# ETAG_v6.net
KiCad netlist of a schematic drawn in EAGLE
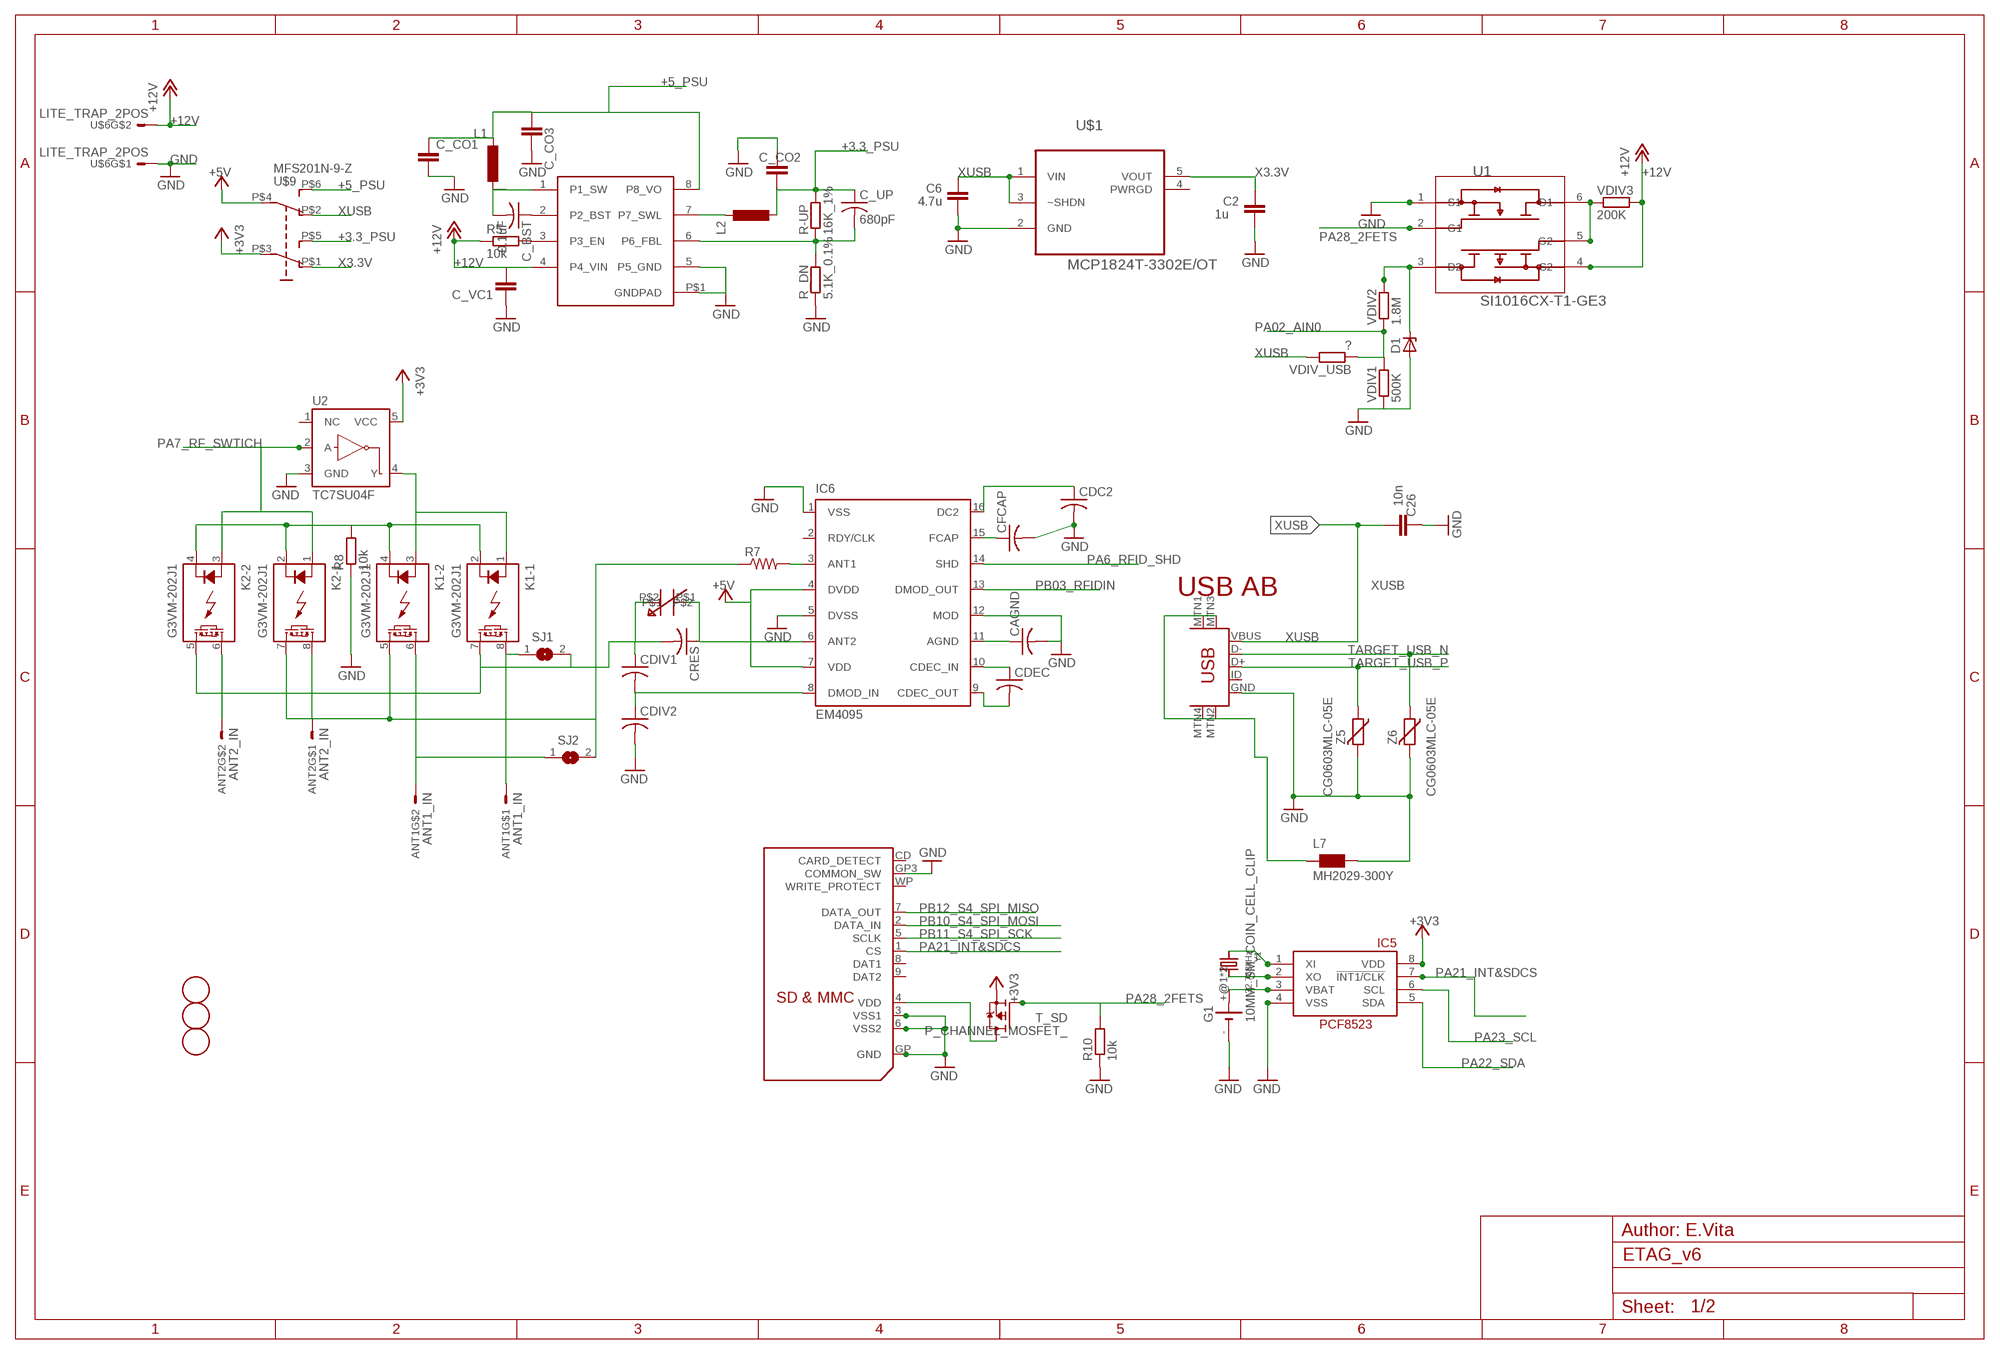
[diagram p0: schematic, sheet 1]
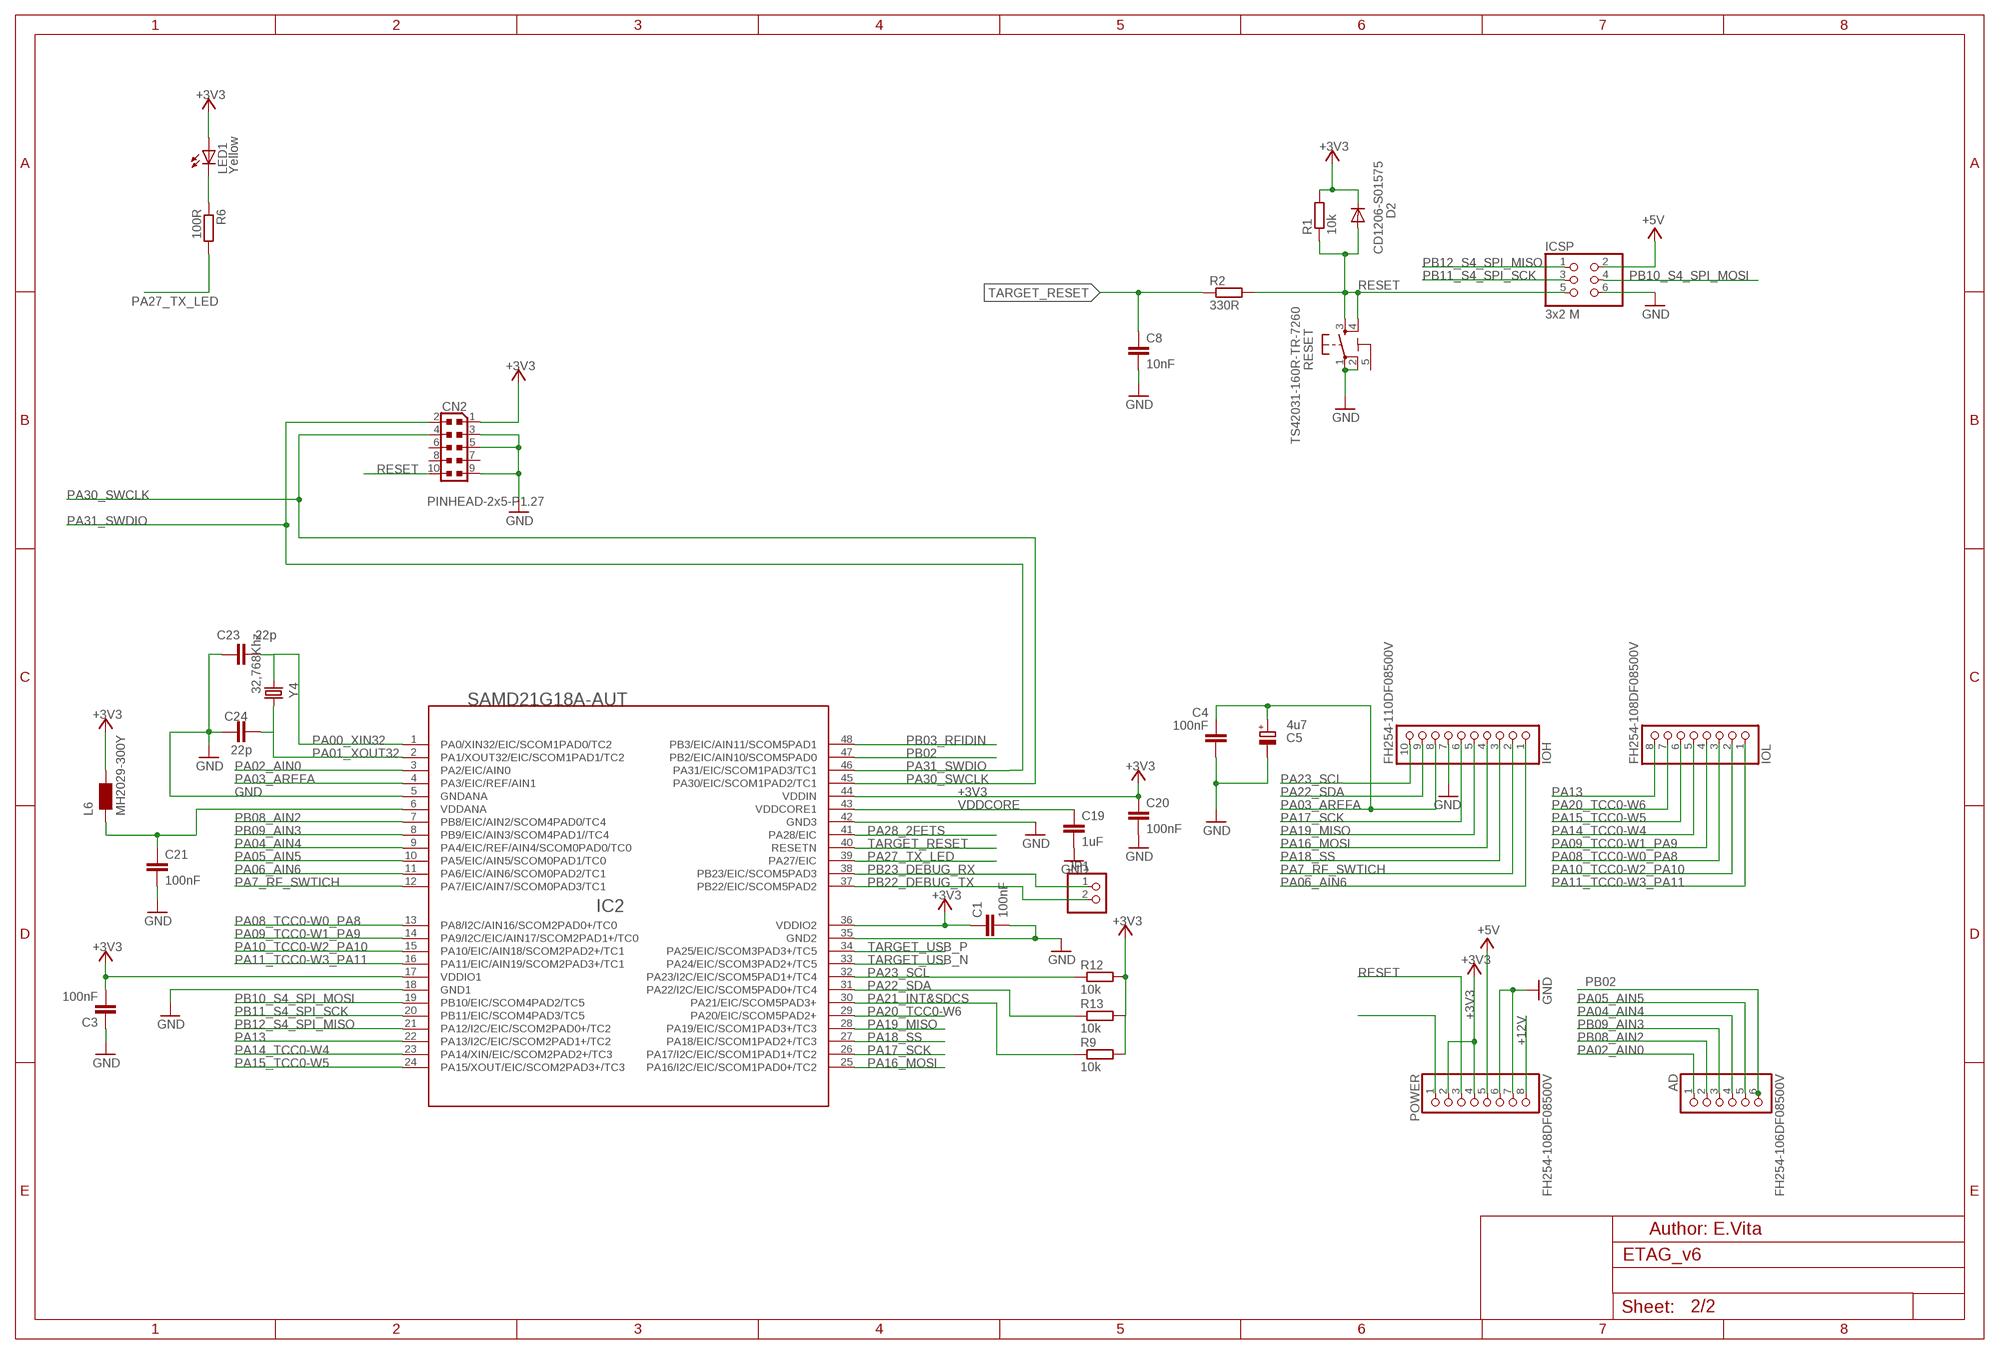
[diagram p1: schematic, sheet 2]

(export (version "E")
  (design (tool "Eeschema 10.0.6"))
  (components
    (comp (ref "AD")
      (value "FH254-106DF08500V")
      (footprint "eagle-import:1X06")
      (fields (field (name "PART_NUMBER") "20TW-535"))
      (libsource (lib "eagle-import") (part "1682_20TW-535_STD"))
    )
    (comp (ref "C1")
      (value "100nF")
      (footprint "eagle-import:C0603-ROUND")
      (fields (field (name "PART_NUMBER") "cl10b104kbnc"))
      (libsource (lib "eagle-import") (part "0015_100NF_0603"))
    )
    (comp (ref "C3")
      (value "100nF")
      (footprint "eagle-import:C0603-ROUND")
      (fields (field (name "PART_NUMBER") "cl10b104kbnc"))
      (libsource (lib "eagle-import") (part "0015_100NF_0603"))
    )
    (comp (ref "C4")
      (value "100nF")
      (footprint "eagle-import:C0603-ROUND")
      (fields (field (name "PART_NUMBER") "cl10b104kbnc"))
      (libsource (lib "eagle-import") (part "0015_100NF_0603"))
    )
    (comp (ref "C5")
      (value "4u7")
      (footprint "eagle-import:SMC_A")
      (fields (field (name "PART_NUMBER") "TAJA475M016RNJ"))
      (libsource (lib "eagle-import") (part "0474_TAJA475M016RNJ"))
    )
    (comp (ref "C8")
      (value "10nF")
      (footprint "eagle-import:C0603-ROUND")
      (fields (field (name "PART_NUMBER") "10nF_0603"))
      (libsource (lib "eagle-import") (part "0142_10NF_0603"))
    )
    (comp (ref "C19")
      (value "1uF")
      (footprint "eagle-import:C0603-ROUND")
      (fields (field (name "PART_NUMBER") "1uF_0603/GRM188R61E105KA12D"))
      (libsource (lib "eagle-import") (part "0006_1UF_0603/GRM188R61E105KA12D"))
    )
    (comp (ref "C20")
      (value "100nF")
      (footprint "eagle-import:C0603-ROUND")
      (fields (field (name "PART_NUMBER") "cl10b104kbnc"))
      (libsource (lib "eagle-import") (part "0015_100NF_0603"))
    )
    (comp (ref "C21")
      (value "100nF")
      (footprint "eagle-import:C0603-ROUND")
      (fields (field (name "PART_NUMBER") "cl10b104kbnc"))
      (libsource (lib "eagle-import") (part "0015_100NF_0603"))
    )
    (comp (ref "C23")
      (value "22p")
      (footprint "eagle-import:C0603-ROUND")
      (fields (field (name "PART_NUMBER") "22pF_0603"))
      (libsource (lib "eagle-import") (part "0014_22PF_0603"))
    )
    (comp (ref "C24")
      (value "22p")
      (footprint "eagle-import:C0603-ROUND")
      (fields (field (name "PART_NUMBER") "22pF_0603"))
      (libsource (lib "eagle-import") (part "0014_22PF_0603"))
    )
    (comp (ref "CN2")
      (value "PINHEAD-2x5-P1.27")
      (footprint "eagle-import:PINHEAD_2X05_127")
      (libsource (lib "eagle-import") (part "0171_PH127-205DF055G00AROUND-PADS"))
    )
    (comp (ref "D2")
      (value "CD1206-S01575")
      (footprint "eagle-import:MINIMELF")
      (libsource (lib "eagle-import") (part "0012_CD1206-S01575"))
    )
    (comp (ref "IC2")
      (value "SAMD21G18A-AUT")
      (footprint "eagle-import:TQFP48-7X7")
      (libsource (lib "eagle-import") (part "1792_SAMD21G18A-AUT"))
    )
    (comp (ref "ICSP")
      (value "3x2 M")
      (footprint "eagle-import:2X03")
      (fields (field (name "PART_NUMBER") "PH254-203DF118A00V"))
      (libsource (lib "eagle-import") (part "0114_PH254-203DF118A00V"))
    )
    (comp (ref "IOH")
      (value "FH254-110DF08500V")
      (footprint "eagle-import:1X10")
      (fields (field (name "PART_NUMBER") "20TW-537"))
      (libsource (lib "eagle-import") (part "1684_20TW-537"))
    )
    (comp (ref "IOL")
      (value "FH254-108DF08500V")
      (footprint "eagle-import:1X08")
      (fields (field (name "PART_NUMBER") "20TW-536"))
      (libsource (lib "eagle-import") (part "1683_20TW-536"))
    )
    (comp (ref "JP1")
      (value "PINHD-1X2")
      (footprint "eagle-import:1X02")
      (libsource (lib "eagle-import") (part "PINHD-1X2"))
    )
    (comp (ref "L6")
      (value "MH2029-300Y")
      (footprint "eagle-import:0805")
      (fields (field (name "PART_NUMBER") "BLM21PG300SN1D_/_MH2029-300Y"))
      (libsource (lib "eagle-import") (part "0001_BLM21PG300SN1D_/_MH2029-300Y"))
    )
    (comp (ref "LED1")
      (value "Yellow")
      (footprint "eagle-import:CHIPLED_0805")
      (fields (field (name "PART_NUMBER") "KPT-2012YC"))
      (libsource (lib "eagle-import") (part "0044_KPT-2012YC"))
    )
    (comp (ref "POWER")
      (value "FH254-108DF08500V")
      (footprint "eagle-import:1X08")
      (fields (field (name "PART_NUMBER") "20TW-536"))
      (libsource (lib "eagle-import") (part "1683_20TW-536"))
    )
    (comp (ref "R1")
      (value "10k")
      (footprint "eagle-import:R0603-ROUND")
      (fields (field (name "PART_NUMBER") "CR0603JW103L"))
      (libsource (lib "eagle-import") (part "0028_CR0603JW103L"))
    )
    (comp (ref "R2")
      (value "330R")
      (footprint "eagle-import:R0603-ROUND")
      (fields (field (name "PART_NUMBER") "330R_0603"))
      (libsource (lib "eagle-import") (part "0049_330R_0603"))
    )
    (comp (ref "R6")
      (value "100R")
      (footprint "eagle-import:R0603-ROUND")
      (fields (field (name "PART_NUMBER") "0R_0603"))
      (libsource (lib "eagle-import") (part "0233_0R_0603"))
    )
    (comp (ref "R9")
      (value "10k")
      (footprint "eagle-import:R0603-ROUND")
      (fields (field (name "PART_NUMBER") "CR0603JW103L"))
      (libsource (lib "eagle-import") (part "0028_CR0603JW103L"))
    )
    (comp (ref "R12")
      (value "10k")
      (footprint "eagle-import:R0603-ROUND")
      (fields (field (name "PART_NUMBER") "CR0603JW103L"))
      (libsource (lib "eagle-import") (part "0028_CR0603JW103L"))
    )
    (comp (ref "R13")
      (value "10k")
      (footprint "eagle-import:R0603-ROUND")
      (fields (field (name "PART_NUMBER") "CR0603JW103L"))
      (libsource (lib "eagle-import") (part "0028_CR0603JW103L"))
    )
    (comp (ref "RESET")
      (value "TS42031-160R-TR-7260")
      (footprint "eagle-import:TS42")
      (fields (field (name "PART_NUMBER") "IT-1157AHNP-160G-G_GTR"))
      (libsource (lib "eagle-import") (part "0946_TS42031-160W-TR-7260"))
    )
    (comp (ref "Y4")
      (value "32,768Khz")
      (footprint "eagle-import:RESONATOR_EPSON_FC_145")
      (fields (field (name "PART_NUMBER") "ABS07-32.768KHZ-T"))
      (libsource (lib "eagle-import") (part "0213_ABS07-32.768KHZ-T"))
    )
    (comp (ref "ANT1")
      (value "ANT1_IN")
      (footprint "eagle-import:LITE_TRAP_MINI")
      (libsource (lib "eagle-import") (part "LITE_TRAP_2POS"))
    )
    (comp (ref "ANT2")
      (value "ANT2_IN")
      (footprint "eagle-import:LITE_TRAP_MINI")
      (libsource (lib "eagle-import") (part "LITE_TRAP_2POS"))
    )
    (comp (ref "C2")
      (value "1u")
      (footprint "eagle-import:C0603-ROUND")
      (fields (field (name "PART_NUMBER") "10nF_0603"))
      (libsource (lib "eagle-import") (part "0142_10NF_0603"))
    )
    (comp (ref "C6")
      (value "4.7u")
      (footprint "eagle-import:C0603-ROUND")
      (fields (field (name "PART_NUMBER") "10nF_0603"))
      (libsource (lib "eagle-import") (part "0142_10NF_0603"))
    )
    (comp (ref "C26")
      (value "10n")
      (footprint "eagle-import:C0603-ROUND")
      (fields (field (name "PART_NUMBER") "10nF_0603"))
      (libsource (lib "eagle-import") (part "0142_10NF_0603"))
    )
    (comp (ref "CAGND")
      (value "C-US")
      (footprint "eagle-import:C0603-ROUND")
      (libsource (lib "eagle-import") (part "C-US"))
    )
    (comp (ref "CDC2")
      (value "C-US")
      (footprint "eagle-import:C0603-ROUND")
      (libsource (lib "eagle-import") (part "C-US"))
    )
    (comp (ref "CDEC")
      (value "C-US")
      (footprint "eagle-import:C0603-ROUND")
      (libsource (lib "eagle-import") (part "C-US"))
    )
    (comp (ref "CDIV1")
      (value "C-USC1206K")
      (footprint "eagle-import:C1206K")
      (libsource (lib "eagle-import") (part "C-USC1206K"))
    )
    (comp (ref "CDIV2")
      (value "C-USC1206K")
      (footprint "eagle-import:C1206K")
      (libsource (lib "eagle-import") (part "C-USC1206K"))
    )
    (comp (ref "CFCAP")
      (value "C-US")
      (footprint "eagle-import:C0603-ROUND")
      (libsource (lib "eagle-import") (part "C-US"))
    )
    (comp (ref "CRES")
      (value "C-USC1206K")
      (footprint "eagle-import:C1206K")
      (libsource (lib "eagle-import") (part "C-USC1206K"))
    )
    (comp (ref "C_BST")
      (value "0.1uF")
      (footprint "eagle-import:C0603-ROUND")
      (libsource (lib "eagle-import") (part "C-US"))
    )
    (comp (ref "C_CO1")
      (value "22uF")
      (footprint "eagle-import:C0805")
      (libsource (lib "eagle-import") (part "C-EUC0805"))
    )
    (comp (ref "C_CO2")
      (value "22uF")
      (footprint "eagle-import:C0805")
      (libsource (lib "eagle-import") (part "C-EUC0805"))
    )
    (comp (ref "C_CO3")
      (value "10uF")
      (footprint "eagle-import:C0805")
      (libsource (lib "eagle-import") (part "C-EUC0805"))
    )
    (comp (ref "C_UP")
      (value "680pF")
      (footprint "eagle-import:C0603-ROUND")
      (libsource (lib "eagle-import") (part "C-US"))
    )
    (comp (ref "C_VC1")
      (value "10uF")
      (footprint "eagle-import:C1210")
      (libsource (lib "eagle-import") (part "C-EUC1210"))
    )
    (comp (ref "D1")
      (value "ZENER-DIODESOD123")
      (footprint "eagle-import:SOD123FL")
      (libsource (lib "eagle-import") (part "ZENER-DIODESOD123"))
    )
    (comp (ref "FD1")
      (value "FIDUCIALMOUNT")
      (footprint "eagle-import:FIDUCIA-MOUNT")
      (libsource (lib "eagle-import") (part "FIDUCIALMOUNT"))
    )
    (comp (ref "FD2")
      (value "FIDUCIALMOUNT")
      (footprint "eagle-import:FIDUCIA-MOUNT")
      (libsource (lib "eagle-import") (part "FIDUCIALMOUNT"))
    )
    (comp (ref "FD3")
      (value "FIDUCIALMOUNT")
      (footprint "eagle-import:FIDUCIA-MOUNT")
      (libsource (lib "eagle-import") (part "FIDUCIALMOUNT"))
    )
    (comp (ref "G1")
      (value "10MM_SM_COIN_CELL_CLIP")
      (footprint "eagle-import:10MM_SM_COIN_CELL_CLIP")
      (libsource (lib "eagle-import") (part "10MM_SM_COIN_CELL_CLIP"))
    )
    (comp (ref "IC5")
      (value "RTC_PCF8523T")
      (footprint "eagle-import:SOIC8_150MIL")
      (libsource (lib "eagle-import") (part "RTC_PCF8523T"))
    )
    (comp (ref "IC6")
      (value "EM4095")
      (footprint "eagle-import:SO16")
      (libsource (lib "eagle-import") (part "EM4095"))
    )
    (comp (ref "K1")
      (value "G3VM-202J1")
      (footprint "eagle-import:SOP08")
      (libsource (lib "eagle-import") (part "AQWSOP21"))
    )
    (comp (ref "K2")
      (value "G3VM-202J1")
      (footprint "eagle-import:SOP08")
      (libsource (lib "eagle-import") (part "AQWSOP21"))
    )
    (comp (ref "L1")
      (value "22uH")
      (footprint "eagle-import:SLF10165")
      (libsource (lib "eagle-import") (part "L-EUSLF_10MM"))
    )
    (comp (ref "L2")
      (value "2.2uH")
      (footprint "eagle-import:L1008(2520METRIC)")
      (libsource (lib "eagle-import") (part "L-EU1008"))
    )
    (comp (ref "L7")
      (value "MH2029-300Y")
      (footprint "eagle-import:0805")
      (fields (field (name "PART_NUMBER") "BLM21PG300SN1D_/_MH2029-300Y"))
      (libsource (lib "eagle-import") (part "0001_BLM21PG300SN1D_/_MH2029-300Y"))
    )
    (comp (ref "R-UP")
      (value "16K_1%")
      (footprint "eagle-import:R0603-ROUND")
      (fields (field (name "PART_NUMBER") "CR0603FW104L"))
      (libsource (lib "eagle-import") (part "2022_CR0603FW104L"))
    )
    (comp (ref "R5")
      (value "10k")
      (footprint "eagle-import:R0603-ROUND")
      (fields (field (name "PART_NUMBER") "CR0603JW103L"))
      (libsource (lib "eagle-import") (part "0028_CR0603JW103L"))
    )
    (comp (ref "R7")
      (value "R-US_R1206")
      (footprint "eagle-import:R1206")
      (libsource (lib "eagle-import") (part "R-US_R1206"))
    )
    (comp (ref "R8")
      (value "10k")
      (footprint "eagle-import:R0603-ROUND")
      (fields (field (name "PART_NUMBER") "CR0603JW103L"))
      (libsource (lib "eagle-import") (part "0028_CR0603JW103L"))
    )
    (comp (ref "R10")
      (value "10k")
      (footprint "eagle-import:R0603-ROUND")
      (fields (field (name "PART_NUMBER") "CR0603JW103L"))
      (libsource (lib "eagle-import") (part "0028_CR0603JW103L"))
    )
    (comp (ref "R_DN")
      (value "5.1K_0.1%")
      (footprint "eagle-import:R0603-ROUND")
      (libsource (lib "eagle-import") (part "2339_"))
    )
    (comp (ref "SJ1")
      (value "SJW")
      (footprint "eagle-import:SJW")
      (libsource (lib "eagle-import") (part "SJW"))
    )
    (comp (ref "SJ2")
      (value "SJW")
      (footprint "eagle-import:SJW")
      (libsource (lib "eagle-import") (part "SJW"))
    )
    (comp (ref "T_SD")
      (value "P_CHANNEL_MOSFET_")
      (footprint "eagle-import:SOT23")
      (libsource (lib "eagle-import") (part "P_CHANNEL_MOSFET_"))
    )
    (comp (ref "U$1")
      (value "MCP1824T-3302E/OT")
      (footprint "eagle-import:SOT95P270X145-5N")
      (libsource (lib "eagle-import") (part "MCP1824T-3302E/OT"))
    )
    (comp (ref "U$3")
      (value "BD93291EFJSOP8_W_GND")
      (footprint "eagle-import:SOP08_GNDPAD")
      (libsource (lib "eagle-import") (part "BD93291EFJSOP8_W_GND"))
    )
    (comp (ref "U$4")
      (value "SDMMC06132")
      (footprint "eagle-import:06132")
      (libsource (lib "eagle-import") (part "SDMMC06132"))
    )
    (comp (ref "U$5")
      (value "USB-MINIB-5PIN")
      (footprint "eagle-import:USB-MINIB")
      (libsource (lib "eagle-import") (part "USB-MINIB-5PIN"))
    )
    (comp (ref "U$6")
      (value "LITE_TRAP_2POS")
      (footprint "eagle-import:LITE_TRAP_MINI")
      (libsource (lib "eagle-import") (part "LITE_TRAP_2POS"))
    )
    (comp (ref "U$9")
      (value "MFS201N-9-Z")
      (footprint "eagle-import:MFS201N-9-Z")
      (libsource (lib "eagle-import") (part "MFS201N-9-Z"))
    )
    (comp (ref "U1")
      (value "SI1016CX-T1-GE3")
      (footprint "eagle-import:SOT50P162X60-6N")
      (libsource (lib "eagle-import") (part "SI1016CX-T1-GE3"))
    )
    (comp (ref "U2")
      (value "TC7SU04F")
      (footprint "eagle-import:SOT23-5")
      (libsource (lib "eagle-import") (part "INVERTER_SOT23-5"))
    )
    (comp (ref "VAR_C")
      (value "TZB4Z100AB10R00")
      (footprint "eagle-import:TZB4Z100AB10R00")
      (libsource (lib "eagle-import") (part "TZB4Z100AB10R00"))
    )
    (comp (ref "VDIV1")
      (value "500K")
      (footprint "eagle-import:R0603-ROUND")
      (libsource (lib "eagle-import") (part "2339_"))
    )
    (comp (ref "VDIV2")
      (value "1.8M")
      (footprint "eagle-import:R0603-ROUND")
      (fields (field (name "PART_NUMBER") "CR0603FW104L"))
      (libsource (lib "eagle-import") (part "2022_CR0603FW104L"))
    )
    (comp (ref "VDIV3")
      (value "200K")
      (footprint "eagle-import:R0603-ROUND")
      (fields (field (name "PART_NUMBER") "CR0603FW104L"))
      (libsource (lib "eagle-import") (part "2022_CR0603FW104L"))
    )
    (comp (ref "VDIV_USB")
      (value "?")
      (footprint "eagle-import:R0603-ROUND")
      (libsource (lib "eagle-import") (part "2339_"))
    )
    (comp (ref "Y1")
      (value "32.768kHz")
      (footprint "eagle-import:CRYSTAL_8X3.8")
      (libsource (lib "eagle-import") (part "CRYSTAL8.0X3.8"))
    )
    (comp (ref "Z5")
      (value "CG0603MLC-05E")
      (footprint "eagle-import:CT_CN0603")
      (fields (field (name "PART_NUMBER") "BRNCG0603MLC-05E"))
      (libsource (lib "eagle-import") (part "0010_BRNCG0603MLC-05E"))
    )
    (comp (ref "Z6")
      (value "CG0603MLC-05E")
      (footprint "eagle-import:CT_CN0603")
      (fields (field (name "PART_NUMBER") "BRNCG0603MLC-05E"))
      (libsource (lib "eagle-import") (part "0010_BRNCG0603MLC-05E"))
    )
  )
  (nets
    (net (code "1") (name "+3.3_PSU") (class "Default")
      (node (ref "C_CO2") (pin "2") (pinfunction "2_2") (pintype "passive"))
      (node (ref "C_UP") (pin "1") (pinfunction "1_1") (pintype "passive"))
      (node (ref "L2") (pin "2") (pinfunction "2_2") (pintype "passive"))
      (node (ref "R-UP") (pin "2") (pinfunction "2_2") (pintype "passive"))
      (node (ref "U$9") (pin "P$5") (pinfunction "S_P$5") (pintype "passive"))
    )
    (net (code "2") (name "+3V3") (class "Default")
      (node (ref "C1") (pin "1") (pinfunction "1_1") (pintype "passive"))
      (node (ref "C20") (pin "1") (pinfunction "1_1") (pintype "passive"))
      (node (ref "C3") (pin "2") (pinfunction "2_2") (pintype "passive"))
      (node (ref "CN2") (pin "1") (pinfunction "1_1") (pintype "passive"))
      (node (ref "D2") (pin "C") (pinfunction "C_C") (pintype "passive"))
      (node (ref "IC2") (pin "17") (pinfunction "VDDIO1_17") (pintype "power_in"))
      (node (ref "IC2") (pin "36") (pinfunction "VDDIO2_36") (pintype "power_in"))
      (node (ref "IC2") (pin "44") (pinfunction "VDDIN_44") (pintype "power_in"))
      (node (ref "IC5") (pin "8") (pinfunction "VDD_8") (pintype "power_in"))
      (node (ref "L6") (pin "2") (pinfunction "2_2") (pintype "passive"))
      (node (ref "LED1") (pin "A") (pinfunction "A_A") (pintype "passive"))
      (node (ref "POWER") (pin "2") (pinfunction "2_2") (pintype "passive"))
      (node (ref "POWER") (pin "4") (pinfunction "4_4") (pintype "passive"))
      (node (ref "R1") (pin "2") (pinfunction "2_2") (pintype "passive"))
      (node (ref "R12") (pin "2") (pinfunction "2_2") (pintype "passive"))
      (node (ref "R13") (pin "2") (pinfunction "2_2") (pintype "passive"))
      (node (ref "R9") (pin "2") (pinfunction "2_2") (pintype "passive"))
      (node (ref "T_SD") (pin "2") (pinfunction "S_2") (pintype "passive"))
      (node (ref "U$9") (pin "P$3") (pinfunction "P_P$3") (pintype "passive"))
      (node (ref "U2") (pin "5") (pinfunction "VCC_5") (pintype "bidirectional"))
    )
    (net (code "3") (name "+5V") (class "Default")
      (node (ref "IC6") (pin "4") (pinfunction "DVDD_4") (pintype "power_in"))
      (node (ref "IC6") (pin "7") (pinfunction "VDD_7") (pintype "power_in"))
      (node (ref "ICSP") (pin "2") (pinfunction "2_2") (pintype "passive"))
      (node (ref "POWER") (pin "5") (pinfunction "5_5") (pintype "passive"))
      (node (ref "U$9") (pin "P$4") (pinfunction "P1_P$4") (pintype "passive"))
    )
    (net (code "4") (name "+5_PSU") (class "Default")
      (node (ref "C_CO1") (pin "1") (pinfunction "1_1") (pintype "passive"))
      (node (ref "C_CO3") (pin "1") (pinfunction "1_1") (pintype "passive"))
      (node (ref "L1") (pin "P$1") (pinfunction "1_P$1") (pintype "passive"))
      (node (ref "U$3") (pin "8") (pinfunction "P8_VO_8") (pintype "bidirectional"))
      (node (ref "U$9") (pin "P$6") (pinfunction "S1_P$6") (pintype "passive"))
    )
    (net (code "5") (name "+12V") (class "Default")
      (node (ref "C_VC1") (pin "2") (pinfunction "2_2") (pintype "passive"))
      (node (ref "POWER") (pin "8") (pinfunction "8_8") (pintype "passive"))
      (node (ref "R5") (pin "1") (pinfunction "1_1") (pintype "passive"))
      (node (ref "U$3") (pin "4") (pinfunction "P4_VIN_4") (pintype "bidirectional"))
      (node (ref "U$6") (pin "P$3") (pinfunction "S_P$3") (pintype "passive"))
      (node (ref "U$6") (pin "P$4") (pinfunction "S_P$4") (pintype "passive"))
      (node (ref "U1") (pin "4") (pinfunction "S2_4") (pintype "passive"))
      (node (ref "VDIV3") (pin "2") (pinfunction "2_2") (pintype "passive"))
    )
    (net (code "6") (name "5-GND") (class "Default")
      (node (ref "RESET") (pin "5") (pinfunction "5-GND_5") (pintype "power_in"))
    )
    (net (code "7") (name "GND") (class "Default")
      (node (ref "C1") (pin "2") (pinfunction "2_2") (pintype "passive"))
      (node (ref "C19") (pin "2") (pinfunction "2_2") (pintype "passive"))
      (node (ref "C2") (pin "1") (pinfunction "1_1") (pintype "passive"))
      (node (ref "C20") (pin "2") (pinfunction "2_2") (pintype "passive"))
      (node (ref "C21") (pin "2") (pinfunction "2_2") (pintype "passive"))
      (node (ref "C23") (pin "1") (pinfunction "1_1") (pintype "passive"))
      (node (ref "C24") (pin "1") (pinfunction "1_1") (pintype "passive"))
      (node (ref "C26") (pin "2") (pinfunction "2_2") (pintype "passive"))
      (node (ref "C3") (pin "1") (pinfunction "1_1") (pintype "passive"))
      (node (ref "C4") (pin "2") (pinfunction "2_2") (pintype "passive"))
      (node (ref "C5") (pin "-") (pinfunction "-_-") (pintype "passive"))
      (node (ref "C6") (pin "1") (pinfunction "1_1") (pintype "passive"))
      (node (ref "C8") (pin "2") (pinfunction "2_2") (pintype "passive"))
      (node (ref "CAGND") (pin "2") (pinfunction "2_2") (pintype "passive"))
      (node (ref "CDC2") (pin "2") (pinfunction "2_2") (pintype "passive"))
      (node (ref "CDIV2") (pin "2") (pinfunction "2_2") (pintype "passive"))
      (node (ref "CFCAP") (pin "2") (pinfunction "2_2") (pintype "passive"))
      (node (ref "CN2") (pin "3") (pinfunction "3_3") (pintype "passive"))
      (node (ref "CN2") (pin "5") (pinfunction "5_5") (pintype "passive"))
      (node (ref "CN2") (pin "9") (pinfunction "9_9") (pintype "passive"))
      (node (ref "C_CO1") (pin "2") (pinfunction "2_2") (pintype "passive"))
      (node (ref "C_CO2") (pin "1") (pinfunction "1_1") (pintype "passive"))
      (node (ref "C_CO3") (pin "2") (pinfunction "2_2") (pintype "passive"))
      (node (ref "C_VC1") (pin "1") (pinfunction "1_1") (pintype "passive"))
      (node (ref "D1") (pin "A") (pinfunction "A_A") (pintype "passive"))
      (node (ref "G1") (pin "-") (pinfunction "-_-") (pintype "passive"))
      (node (ref "IC2") (pin "18") (pinfunction "GND1_18") (pintype "power_in"))
      (node (ref "IC2") (pin "35") (pinfunction "GND2_35") (pintype "power_in"))
      (node (ref "IC2") (pin "42") (pinfunction "GND3_42") (pintype "power_in"))
      (node (ref "IC2") (pin "5") (pinfunction "GNDANA_5") (pintype "power_in"))
      (node (ref "IC5") (pin "4") (pinfunction "VSS_4") (pintype "power_in"))
      (node (ref "IC6") (pin "1") (pinfunction "VSS_1") (pintype "power_in"))
      (node (ref "IC6") (pin "12") (pinfunction "MOD_12") (pintype "input"))
      (node (ref "IC6") (pin "5") (pinfunction "DVSS_5") (pintype "power_in"))
      (node (ref "ICSP") (pin "6") (pinfunction "6_6") (pintype "passive"))
      (node (ref "IOH") (pin "7") (pinfunction "7_7") (pintype "passive"))
      (node (ref "L7") (pin "2") (pinfunction "2_2") (pintype "passive"))
      (node (ref "POWER") (pin "6") (pinfunction "6_6") (pintype "passive"))
      (node (ref "POWER") (pin "7") (pinfunction "7_7") (pintype "passive"))
      (node (ref "R10") (pin "1") (pinfunction "1_1") (pintype "passive"))
      (node (ref "R8") (pin "1") (pinfunction "1_1") (pintype "passive"))
      (node (ref "RESET") (pin "1") (pinfunction "1_1") (pintype "passive"))
      (node (ref "RESET") (pin "2") (pinfunction "2_2") (pintype "passive"))
      (node (ref "R_DN") (pin "1") (pinfunction "1_1") (pintype "passive"))
      (node (ref "U$1") (pin "2") (pinfunction "GND_2") (pintype "passive"))
      (node (ref "U$3") (pin "5") (pinfunction "P5_GND_5") (pintype "bidirectional"))
      (node (ref "U$3") (pin "P$1") (pinfunction "GNDPAD_P$1") (pintype "bidirectional"))
      (node (ref "U$4") (pin "3") (pinfunction "VSS1_3") (pintype "power_in"))
      (node (ref "U$4") (pin "6") (pinfunction "VSS2_6") (pintype "power_in"))
      (node (ref "U$4") (pin "GP") (pinfunction "GND_GP") (pintype "power_in"))
      (node (ref "U$4") (pin "GP3") (pinfunction "COMMON_SW_GP3") (pintype "passive"))
      (node (ref "U$5") (pin "GND") (pinfunction "GND_GND") (pintype "bidirectional"))
      (node (ref "U$6") (pin "P$1") (pinfunction "S_P$1") (pintype "passive"))
      (node (ref "U$6") (pin "P$2") (pinfunction "S_P$2") (pintype "passive"))
      (node (ref "U1") (pin "1") (pinfunction "S1_1") (pintype "passive"))
      (node (ref "U2") (pin "3") (pinfunction "GND_3") (pintype "bidirectional"))
      (node (ref "VDIV1") (pin "1") (pinfunction "1_1") (pintype "passive"))
      (node (ref "Z5") (pin "2") (pinfunction "2_2") (pintype "passive"))
      (node (ref "Z6") (pin "2") (pinfunction "2_2") (pintype "passive"))
    )
    (net (code "8") (name "Net-(IC2-VDDANA)") (class "Default")
      (node (ref "C21") (pin "1") (pinfunction "1_1") (pintype "passive"))
      (node (ref "IC2") (pin "6") (pinfunction "VDDANA_6") (pintype "power_in"))
      (node (ref "L6") (pin "1") (pinfunction "1_1") (pintype "passive"))
    )
    (net (code "9") (name "Net-(IC5-VBAT)") (class "Default")
      (node (ref "G1") (pin "+@1") (pinfunction "+_+@1") (pintype "passive"))
      (node (ref "G1") (pin "+@2") (pinfunction "+_+@2") (pintype "passive"))
      (node (ref "IC5") (pin "3") (pinfunction "VBAT_3") (pintype "power_in"))
    )
    (net (code "10") (name "Net-(IC5-XI)") (class "Default")
      (node (ref "IC5") (pin "1") (pinfunction "XI_1") (pintype "input"))
      (node (ref "Y1") (pin "P$1") (pinfunction "1_P$1") (pintype "passive"))
    )
    (net (code "11") (name "Net-(IC5-XO)") (class "Default")
      (node (ref "IC5") (pin "2") (pinfunction "XO_2") (pintype "output"))
      (node (ref "Y1") (pin "P$4") (pinfunction "2_P$4") (pintype "passive"))
    )
    (net (code "12") (name "Net-(IC6-AGND)") (class "Default")
      (node (ref "CAGND") (pin "1") (pinfunction "1_1") (pintype "passive"))
      (node (ref "IC6") (pin "11") (pinfunction "AGND_11") (pintype "power_in"))
    )
    (net (code "13") (name "Net-(IC6-ANT1)") (class "Default")
      (node (ref "IC6") (pin "3") (pinfunction "ANT1_3") (pintype "passive"))
      (node (ref "R7") (pin "2") (pinfunction "2_2") (pintype "passive"))
    )
    (net (code "14") (name "Net-(IC6-ANT2)") (class "Default")
      (node (ref "CRES") (pin "1") (pinfunction "1_1") (pintype "passive"))
      (node (ref "IC6") (pin "6") (pinfunction "ANT2_6") (pintype "passive"))
      (node (ref "VAR_C") (pin "P$1") (pinfunction "P$1_P$1") (pintype "bidirectional"))
    )
    (net (code "15") (name "Net-(IC6-CDEC_IN)") (class "Default")
      (node (ref "CDEC") (pin "1") (pinfunction "1_1") (pintype "passive"))
      (node (ref "IC6") (pin "10") (pinfunction "CDEC_IN_10") (pintype "input"))
    )
    (net (code "16") (name "Net-(IC6-CDEC_OUT)") (class "Default")
      (node (ref "CDEC") (pin "2") (pinfunction "2_2") (pintype "passive"))
      (node (ref "IC6") (pin "9") (pinfunction "CDEC_OUT_9") (pintype "output"))
    )
    (net (code "17") (name "Net-(IC6-DC2)") (class "Default")
      (node (ref "CDC2") (pin "1") (pinfunction "1_1") (pintype "passive"))
      (node (ref "IC6") (pin "16") (pinfunction "DC2_16") (pintype "passive"))
    )
    (net (code "18") (name "Net-(IC6-DMOD_IN)") (class "Default")
      (node (ref "CDIV1") (pin "2") (pinfunction "2_2") (pintype "passive"))
      (node (ref "CDIV2") (pin "1") (pinfunction "1_1") (pintype "passive"))
      (node (ref "IC6") (pin "8") (pinfunction "DMOD_IN_8") (pintype "input"))
    )
    (net (code "19") (name "Net-(IC6-FCAP)") (class "Default")
      (node (ref "CFCAP") (pin "1") (pinfunction "1_1") (pintype "passive"))
      (node (ref "IC6") (pin "15") (pinfunction "FCAP_15") (pintype "passive"))
    )
    (net (code "20") (name "Net-(K1A-A)") (class "Default")
      (node (ref "K1") (pin "1") (pinfunction "A_1") (pintype "passive"))
      (node (ref "K1") (pin "3") (pinfunction "A_3") (pintype "passive"))
      (node (ref "U2") (pin "4") (pinfunction "Y_4") (pintype "bidirectional"))
    )
    (net (code "21") (name "Net-(K1A-D1)") (class "Default")
      (node (ref "ANT1") (pin "P$1") (pinfunction "S_P$1") (pintype "passive"))
      (node (ref "ANT1") (pin "P$2") (pinfunction "S_P$2") (pintype "passive"))
      (node (ref "K1") (pin "8") (pinfunction "D1_8") (pintype "passive"))
      (node (ref "SJ1") (pin "1") (pinfunction "1_1") (pintype "passive"))
    )
    (net (code "22") (name "Net-(K1A-D2)") (class "Default")
      (node (ref "CDIV1") (pin "1") (pinfunction "1_1") (pintype "passive"))
      (node (ref "CRES") (pin "2") (pinfunction "2_2") (pintype "passive"))
      (node (ref "K1") (pin "7") (pinfunction "D2_7") (pintype "passive"))
      (node (ref "K2") (pin "5") (pinfunction "D2_5") (pintype "passive"))
      (node (ref "SJ1") (pin "2") (pinfunction "2_2") (pintype "passive"))
      (node (ref "VAR_C") (pin "P$2") (pinfunction "P$2_P$2") (pintype "bidirectional"))
    )
    (net (code "23") (name "Net-(K1A-K)") (class "Default")
      (node (ref "K1") (pin "2") (pinfunction "K_2") (pintype "passive"))
      (node (ref "K1") (pin "4") (pinfunction "K_4") (pintype "passive"))
      (node (ref "K2") (pin "2") (pinfunction "K_2") (pintype "passive"))
      (node (ref "K2") (pin "4") (pinfunction "K_4") (pintype "passive"))
      (node (ref "R8") (pin "2") (pinfunction "2_2") (pintype "passive"))
    )
    (net (code "24") (name "Net-(K1B-D1)") (class "Default")
      (node (ref "ANT1") (pin "P$3") (pinfunction "S_P$3") (pintype "passive"))
      (node (ref "ANT1") (pin "P$4") (pinfunction "S_P$4") (pintype "passive"))
      (node (ref "K1") (pin "6") (pinfunction "D1_6") (pintype "passive"))
      (node (ref "SJ2") (pin "1") (pinfunction "1_1") (pintype "passive"))
    )
    (net (code "25") (name "Net-(K1B-D2)") (class "Default")
      (node (ref "K1") (pin "5") (pinfunction "D2_5") (pintype "passive"))
      (node (ref "K2") (pin "7") (pinfunction "D2_7") (pintype "passive"))
      (node (ref "R7") (pin "1") (pinfunction "1_1") (pintype "passive"))
      (node (ref "SJ2") (pin "2") (pinfunction "2_2") (pintype "passive"))
    )
    (net (code "26") (name "Net-(K2A-D1)") (class "Default")
      (node (ref "ANT2") (pin "P$1") (pinfunction "S_P$1") (pintype "passive"))
      (node (ref "ANT2") (pin "P$2") (pinfunction "S_P$2") (pintype "passive"))
      (node (ref "K2") (pin "8") (pinfunction "D1_8") (pintype "passive"))
    )
    (net (code "27") (name "Net-(K2B-D1)") (class "Default")
      (node (ref "ANT2") (pin "P$3") (pinfunction "S_P$3") (pintype "passive"))
      (node (ref "ANT2") (pin "P$4") (pinfunction "S_P$4") (pintype "passive"))
      (node (ref "K2") (pin "6") (pinfunction "D1_6") (pintype "passive"))
    )
    (net (code "28") (name "Net-(L1-2)") (class "Default")
      (node (ref "C_BST") (pin "2") (pinfunction "2_2") (pintype "passive"))
      (node (ref "L1") (pin "P$2") (pinfunction "2_P$2") (pintype "passive"))
      (node (ref "U$3") (pin "1") (pinfunction "P1_SW_1") (pintype "bidirectional"))
    )
    (net (code "29") (name "Net-(LED1-PadC)") (class "Default")
      (node (ref "LED1") (pin "C") (pinfunction "C_C") (pintype "passive"))
      (node (ref "R6") (pin "1") (pinfunction "1_1") (pintype "passive"))
    )
    (net (code "30") (name "Net-(T_SD-D)") (class "Default")
      (node (ref "T_SD") (pin "3") (pinfunction "D_3") (pintype "passive"))
      (node (ref "U$4") (pin "4") (pinfunction "VDD_4") (pintype "power_in"))
    )
    (net (code "31") (name "Net-(U$3-P2_BST)") (class "Default")
      (node (ref "C_BST") (pin "1") (pinfunction "1_1") (pintype "passive"))
      (node (ref "U$3") (pin "2") (pinfunction "P2_BST_2") (pintype "bidirectional"))
    )
    (net (code "32") (name "Net-(U$3-P3_EN)") (class "Default")
      (node (ref "R5") (pin "2") (pinfunction "2_2") (pintype "passive"))
      (node (ref "U$3") (pin "3") (pinfunction "P3_EN_3") (pintype "bidirectional"))
    )
    (net (code "33") (name "Net-(U$3-P6_FBL)") (class "Default")
      (node (ref "C_UP") (pin "2") (pinfunction "2_2") (pintype "passive"))
      (node (ref "R-UP") (pin "1") (pinfunction "1_1") (pintype "passive"))
      (node (ref "R_DN") (pin "2") (pinfunction "2_2") (pintype "passive"))
      (node (ref "U$3") (pin "6") (pinfunction "P6_FBL_6") (pintype "bidirectional"))
    )
    (net (code "34") (name "Net-(U$3-P7_SWL)") (class "Default")
      (node (ref "L2") (pin "1") (pinfunction "1_1") (pintype "passive"))
      (node (ref "U$3") (pin "7") (pinfunction "P7_SWL_7") (pintype "bidirectional"))
    )
    (net (code "35") (name "Net-(U$5-MTN1)") (class "Default")
      (node (ref "L7") (pin "1") (pinfunction "1_1") (pintype "passive"))
      (node (ref "U$5") (pin "MTN1") (pinfunction "MTN2_MTN1") (pintype "bidirectional"))
      (node (ref "U$5") (pin "MTN2") (pinfunction "MTN3_MTN2") (pintype "bidirectional"))
      (node (ref "U$5") (pin "MTN3") (pinfunction "MTN1_MTN3") (pintype "bidirectional"))
      (node (ref "U$5") (pin "MTN4") (pinfunction "MTN4_MTN4") (pintype "bidirectional"))
    )
    (net (code "36") (name "Net-(U1-D1)") (class "Default")
      (node (ref "U1") (pin "5") (pinfunction "G2_5") (pintype "passive"))
      (node (ref "U1") (pin "6") (pinfunction "D1_6") (pintype "passive"))
      (node (ref "VDIV3") (pin "1") (pinfunction "1_1") (pintype "passive"))
    )
    (net (code "37") (name "Net-(U1-D2)") (class "Default")
      (node (ref "D1") (pin "C") (pinfunction "C_C") (pintype "passive"))
      (node (ref "U1") (pin "3") (pinfunction "D2_3") (pintype "passive"))
      (node (ref "VDIV2") (pin "2") (pinfunction "2_2") (pintype "passive"))
    )
    (net (code "38") (name "PA00_XIN32") (class "Default")
      (node (ref "C23") (pin "2") (pinfunction "2_2") (pintype "passive"))
      (node (ref "IC2") (pin "1") (pinfunction "PA0/XIN32/EIC/SCOM1PAD0/TC2_1") (pintype "bidirectional"))
      (node (ref "Y4") (pin "P$1") (pinfunction "1_P$1") (pintype "bidirectional"))
    )
    (net (code "39") (name "PA01_XOUT32") (class "Default")
      (node (ref "C24") (pin "2") (pinfunction "2_2") (pintype "passive"))
      (node (ref "IC2") (pin "2") (pinfunction "PA1/XOUT32/EIC/SCOM1PAD1/TC2_2") (pintype "bidirectional"))
      (node (ref "Y4") (pin "P$2") (pinfunction "2_P$2") (pintype "bidirectional"))
    )
    (net (code "40") (name "PA02_AIN0") (class "Default")
      (node (ref "AD") (pin "1") (pinfunction "1_1") (pintype "passive"))
      (node (ref "IC2") (pin "3") (pinfunction "PA2/EIC/AIN0_3") (pintype "bidirectional"))
      (node (ref "VDIV1") (pin "2") (pinfunction "2_2") (pintype "passive"))
      (node (ref "VDIV2") (pin "1") (pinfunction "1_1") (pintype "passive"))
      (node (ref "VDIV_USB") (pin "1") (pinfunction "1_1") (pintype "passive"))
    )
    (net (code "41") (name "PA03_AREFA") (class "Default")
      (node (ref "C4") (pin "1") (pinfunction "1_1") (pintype "passive"))
      (node (ref "C5") (pin "+") (pinfunction "+_+") (pintype "passive"))
      (node (ref "IC2") (pin "4") (pinfunction "PA3/EIC/REF/AIN1_4") (pintype "bidirectional"))
      (node (ref "IOH") (pin "8") (pinfunction "8_8") (pintype "passive"))
    )
    (net (code "42") (name "PA04_AIN4") (class "Default")
      (node (ref "AD") (pin "4") (pinfunction "4_4") (pintype "passive"))
      (node (ref "IC2") (pin "9") (pinfunction "PA4/EIC/REF/AIN4/SCOM0PAD0/TC0_9") (pintype "bidirectional"))
    )
    (net (code "43") (name "PA05_AIN5") (class "Default")
      (node (ref "AD") (pin "5") (pinfunction "5_5") (pintype "passive"))
      (node (ref "IC2") (pin "10") (pinfunction "PA5/EIC/AIN5/SCOM0PAD1/TC0_10") (pintype "bidirectional"))
    )
    (net (code "44") (name "PA06_AIN6") (class "Default")
      (node (ref "IC2") (pin "11") (pinfunction "PA6/EIC/AIN6/SCOM0PAD2/TC1_11") (pintype "bidirectional"))
      (node (ref "IOH") (pin "1") (pinfunction "1_1") (pintype "passive"))
    )
    (net (code "45") (name "PA6_RFID_SHD") (class "Default")
      (node (ref "IC6") (pin "14") (pinfunction "SHD_14") (pintype "input"))
    )
    (net (code "46") (name "PA7_RF_SWTICH") (class "Default")
      (node (ref "IC2") (pin "12") (pinfunction "PA7/EIC/AIN7/SCOM0PAD3/TC1_12") (pintype "bidirectional"))
      (node (ref "IOH") (pin "2") (pinfunction "2_2") (pintype "passive"))
      (node (ref "K2") (pin "1") (pinfunction "A_1") (pintype "passive"))
      (node (ref "K2") (pin "3") (pinfunction "A_3") (pintype "passive"))
      (node (ref "U2") (pin "2") (pinfunction "A_2") (pintype "bidirectional"))
    )
    (net (code "47") (name "PA08_TCC0-W0_PA8") (class "Default")
      (node (ref "IC2") (pin "13") (pinfunction "PA8/I2C/AIN16/SCOM2PAD0+/TC0_13") (pintype "bidirectional"))
      (node (ref "IOL") (pin "3") (pinfunction "3_3") (pintype "passive"))
    )
    (net (code "48") (name "PA09_TCC0-W1_PA9") (class "Default")
      (node (ref "IC2") (pin "14") (pinfunction "PA9/I2C/EIC/AIN17/SCOM2PAD1+/TC0_14") (pintype "bidirectional"))
      (node (ref "IOL") (pin "4") (pinfunction "4_4") (pintype "passive"))
    )
    (net (code "49") (name "PA10_TCC0-W2_PA10") (class "Default")
      (node (ref "IC2") (pin "15") (pinfunction "PA10/EIC/AIN18/SCOM2PAD2+/TC1_15") (pintype "bidirectional"))
      (node (ref "IOL") (pin "2") (pinfunction "2_2") (pintype "passive"))
    )
    (net (code "50") (name "PA11_TCC0-W3_PA11") (class "Default")
      (node (ref "IC2") (pin "16") (pinfunction "PA11/EIC/AIN19/SCOM2PAD3+/TC1_16") (pintype "bidirectional"))
      (node (ref "IOL") (pin "1") (pinfunction "1_1") (pintype "passive"))
    )
    (net (code "51") (name "PA13") (class "Default")
      (node (ref "IC2") (pin "22") (pinfunction "PA13/I2C/EIC/SCOM2PAD1+/TC2_22") (pintype "bidirectional"))
      (node (ref "IOL") (pin "8") (pinfunction "8_8") (pintype "passive"))
    )
    (net (code "52") (name "PA14_TCC0-W4") (class "Default")
      (node (ref "IC2") (pin "23") (pinfunction "PA14/XIN/EIC/SCOM2PAD2+/TC3_23") (pintype "bidirectional"))
      (node (ref "IOL") (pin "5") (pinfunction "5_5") (pintype "passive"))
    )
    (net (code "53") (name "PA15_TCC0-W5") (class "Default")
      (node (ref "IC2") (pin "24") (pinfunction "PA15/XOUT/EIC/SCOM2PAD3+/TC3_24") (pintype "bidirectional"))
      (node (ref "IOL") (pin "6") (pinfunction "6_6") (pintype "passive"))
    )
    (net (code "54") (name "PA16_MOSI") (class "Default")
      (node (ref "IC2") (pin "25") (pinfunction "PA16/I2C/EIC/SCOM1PAD0+/TC2_25") (pintype "bidirectional"))
      (node (ref "IOH") (pin "4") (pinfunction "4_4") (pintype "passive"))
    )
    (net (code "55") (name "PA17_SCK") (class "Default")
      (node (ref "IC2") (pin "26") (pinfunction "PA17/I2C/EIC/SCOM1PAD1+/TC2_26") (pintype "bidirectional"))
      (node (ref "IOH") (pin "6") (pinfunction "6_6") (pintype "passive"))
    )
    (net (code "56") (name "PA18_SS") (class "Default")
      (node (ref "IC2") (pin "27") (pinfunction "PA18/EIC/SCOM1PAD2+/TC3_27") (pintype "bidirectional"))
      (node (ref "IOH") (pin "3") (pinfunction "3_3") (pintype "passive"))
    )
    (net (code "57") (name "PA19_MISO") (class "Default")
      (node (ref "IC2") (pin "28") (pinfunction "PA19/EIC/SCOM1PAD3+/TC3_28") (pintype "bidirectional"))
      (node (ref "IOH") (pin "5") (pinfunction "5_5") (pintype "passive"))
    )
    (net (code "58") (name "PA20_TCC0-W6") (class "Default")
      (node (ref "IC2") (pin "29") (pinfunction "PA20/EIC/SCOM5PAD2+_29") (pintype "bidirectional"))
      (node (ref "IOL") (pin "7") (pinfunction "7_7") (pintype "passive"))
    )
    (net (code "59") (name "PA21_INT&SDCS") (class "Default")
      (node (ref "IC2") (pin "30") (pinfunction "PA21/EIC/SCOM5PAD3+_30") (pintype "bidirectional"))
      (node (ref "IC5") (pin "7") (pinfunction "~{INT1/CLK}_7") (pintype "output"))
      (node (ref "R9") (pin "1") (pinfunction "1_1") (pintype "passive"))
      (node (ref "U$4") (pin "1") (pinfunction "CS_1") (pintype "input"))
    )
    (net (code "60") (name "PA22_SDA") (class "Default")
      (node (ref "IC2") (pin "31") (pinfunction "PA22/I2C/EIC/SCOM5PAD0+/TC4_31") (pintype "bidirectional"))
      (node (ref "IC5") (pin "5") (pinfunction "SDA_5") (pintype "bidirectional"))
      (node (ref "IOH") (pin "9") (pinfunction "9_9") (pintype "passive"))
      (node (ref "R13") (pin "1") (pinfunction "1_1") (pintype "passive"))
    )
    (net (code "61") (name "PA23_SCL") (class "Default")
      (node (ref "IC2") (pin "32") (pinfunction "PA23/I2C/EIC/SCOM5PAD1+/TC4_32") (pintype "bidirectional"))
      (node (ref "IC5") (pin "6") (pinfunction "SCL_6") (pintype "bidirectional"))
      (node (ref "IOH") (pin "10") (pinfunction "10_10") (pintype "passive"))
      (node (ref "R12") (pin "1") (pinfunction "1_1") (pintype "passive"))
    )
    (net (code "62") (name "PA27_TX_LED") (class "Default")
      (node (ref "IC2") (pin "39") (pinfunction "PA27/EIC_39") (pintype "bidirectional"))
      (node (ref "R6") (pin "2") (pinfunction "2_2") (pintype "passive"))
    )
    (net (code "63") (name "PA28_2FETS") (class "Default")
      (node (ref "IC2") (pin "41") (pinfunction "PA28/EIC_41") (pintype "bidirectional"))
      (node (ref "R10") (pin "2") (pinfunction "2_2") (pintype "passive"))
      (node (ref "T_SD") (pin "1") (pinfunction "G_1") (pintype "passive"))
      (node (ref "U1") (pin "2") (pinfunction "G1_2") (pintype "passive"))
    )
    (net (code "64") (name "PA30_SWCLK") (class "Default")
      (node (ref "CN2") (pin "4") (pinfunction "4_4") (pintype "passive"))
      (node (ref "IC2") (pin "45") (pinfunction "PA30/EIC/SCOM1PAD2/TC1_45") (pintype "bidirectional"))
    )
    (net (code "65") (name "PA31_SWDIO") (class "Default")
      (node (ref "CN2") (pin "2") (pinfunction "2_2") (pintype "passive"))
      (node (ref "IC2") (pin "46") (pinfunction "PA31/EIC/SCOM1PAD3/TC1_46") (pintype "bidirectional"))
    )
    (net (code "66") (name "PB02") (class "Default")
      (node (ref "AD") (pin "6") (pinfunction "6_6") (pintype "passive"))
      (node (ref "IC2") (pin "47") (pinfunction "PB2/EIC/AIN10/SCOM5PAD0_47") (pintype "bidirectional"))
    )
    (net (code "67") (name "PB03_RFIDIN") (class "Default")
      (node (ref "IC2") (pin "48") (pinfunction "PB3/EIC/AIN11/SCOM5PAD1_48") (pintype "bidirectional"))
      (node (ref "IC6") (pin "13") (pinfunction "DMOD_OUT_13") (pintype "output"))
    )
    (net (code "68") (name "PB08_AIN2") (class "Default")
      (node (ref "AD") (pin "2") (pinfunction "2_2") (pintype "passive"))
      (node (ref "IC2") (pin "7") (pinfunction "PB8/EIC/AIN2/SCOM4PAD0/TC4_7") (pintype "bidirectional"))
    )
    (net (code "69") (name "PB09_AIN3") (class "Default")
      (node (ref "AD") (pin "3") (pinfunction "3_3") (pintype "passive"))
      (node (ref "IC2") (pin "8") (pinfunction "PB9/EIC/AIN3/SCOM4PAD1//TC4_8") (pintype "bidirectional"))
    )
    (net (code "70") (name "PB10_S4_SPI_MOSI") (class "Default")
      (node (ref "IC2") (pin "19") (pinfunction "PB10/EIC/SCOM4PAD2/TC5_19") (pintype "bidirectional"))
      (node (ref "ICSP") (pin "4") (pinfunction "4_4") (pintype "passive"))
      (node (ref "U$4") (pin "2") (pinfunction "DATA_IN_2") (pintype "input"))
    )
    (net (code "71") (name "PB11_S4_SPI_SCK") (class "Default")
      (node (ref "IC2") (pin "20") (pinfunction "PB11/EIC/SCOM4PAD3/TC5_20") (pintype "bidirectional"))
      (node (ref "ICSP") (pin "3") (pinfunction "3_3") (pintype "passive"))
      (node (ref "U$4") (pin "5") (pinfunction "SCLK_5") (pintype "input"))
    )
    (net (code "72") (name "PB12_S4_SPI_MISO") (class "Default")
      (node (ref "IC2") (pin "21") (pinfunction "PA12/I2C/EIC/SCOM2PAD0+/TC2_21") (pintype "bidirectional"))
      (node (ref "ICSP") (pin "1") (pinfunction "1_1") (pintype "passive"))
      (node (ref "U$4") (pin "7") (pinfunction "DATA_OUT_7") (pintype "output"))
    )
    (net (code "73") (name "PB22_DEBUG_TX") (class "Default")
      (node (ref "IC2") (pin "37") (pinfunction "PB22/EIC/SCOM5PAD2_37") (pintype "bidirectional"))
      (node (ref "JP1") (pin "2") (pinfunction "2_2") (pintype "passive"))
    )
    (net (code "74") (name "PB23_DEBUG_RX") (class "Default")
      (node (ref "IC2") (pin "38") (pinfunction "PB23/EIC/SCOM5PAD3_38") (pintype "bidirectional"))
      (node (ref "JP1") (pin "1") (pinfunction "1_1") (pintype "passive"))
    )
    (net (code "75") (name "RESET") (class "Default")
      (node (ref "CN2") (pin "10") (pinfunction "10_10") (pintype "passive"))
      (node (ref "D2") (pin "A") (pinfunction "A_A") (pintype "passive"))
      (node (ref "ICSP") (pin "5") (pinfunction "5_5") (pintype "passive"))
      (node (ref "POWER") (pin "3") (pinfunction "3_3") (pintype "passive"))
      (node (ref "R1") (pin "1") (pinfunction "1_1") (pintype "passive"))
      (node (ref "R2") (pin "2") (pinfunction "2_2") (pintype "passive"))
      (node (ref "RESET") (pin "3") (pinfunction "3_3") (pintype "passive"))
      (node (ref "RESET") (pin "4") (pinfunction "4_4") (pintype "passive"))
    )
    (net (code "76") (name "TARGET_RESET") (class "Default")
      (node (ref "C8") (pin "1") (pinfunction "1_1") (pintype "passive"))
      (node (ref "IC2") (pin "40") (pinfunction "RESETN_40") (pintype "bidirectional"))
      (node (ref "R2") (pin "1") (pinfunction "1_1") (pintype "passive"))
    )
    (net (code "77") (name "TARGET_USB_N") (class "Default")
      (node (ref "IC2") (pin "33") (pinfunction "PA24/EIC/SCOM3PAD2+/TC5_33") (pintype "bidirectional"))
      (node (ref "U$5") (pin "D-") (pinfunction "D-_D-") (pintype "bidirectional"))
      (node (ref "Z6") (pin "1") (pinfunction "1_1") (pintype "passive"))
    )
    (net (code "78") (name "TARGET_USB_P") (class "Default")
      (node (ref "IC2") (pin "34") (pinfunction "PA25/EIC/SCOM3PAD3+/TC5_34") (pintype "bidirectional"))
      (node (ref "U$5") (pin "D+") (pinfunction "D+_D+") (pintype "bidirectional"))
      (node (ref "Z5") (pin "1") (pinfunction "1_1") (pintype "passive"))
    )
    (net (code "79") (name "VDDCORE") (class "Default")
      (node (ref "C19") (pin "1") (pinfunction "1_1") (pintype "passive"))
      (node (ref "IC2") (pin "43") (pinfunction "VDDCORE1_43") (pintype "input"))
    )
    (net (code "80") (name "X3.3V") (class "Default")
      (node (ref "C2") (pin "2") (pinfunction "2_2") (pintype "passive"))
      (node (ref "U$1") (pin "5") (pinfunction "VOUT_5") (pintype "output"))
      (node (ref "U$9") (pin "P$1") (pinfunction "O_P$1") (pintype "passive"))
    )
    (net (code "81") (name "XUSB") (class "Default")
      (node (ref "C26") (pin "1") (pinfunction "1_1") (pintype "passive"))
      (node (ref "C6") (pin "2") (pinfunction "2_2") (pintype "passive"))
      (node (ref "U$1") (pin "1") (pinfunction "VIN_1") (pintype "input"))
      (node (ref "U$1") (pin "3") (pinfunction "~{SHDN}_3") (pintype "input"))
      (node (ref "U$5") (pin "VBUS") (pinfunction "VBUS_VBUS") (pintype "bidirectional"))
      (node (ref "U$9") (pin "P$2") (pinfunction "O1_P$2") (pintype "passive"))
      (node (ref "VDIV_USB") (pin "2") (pinfunction "2_2") (pintype "passive"))
    )
    (net (code "82") (name "unconnected-(CN2-Pad6)") (class "Default")
      (node (ref "CN2") (pin "6") (pinfunction "6_6") (pintype "passive"))
    )
    (net (code "83") (name "unconnected-(CN2-Pad7)") (class "Default")
      (node (ref "CN2") (pin "7") (pinfunction "7_7") (pintype "passive"))
    )
    (net (code "84") (name "unconnected-(CN2-Pad8)") (class "Default")
      (node (ref "CN2") (pin "8") (pinfunction "8_8") (pintype "passive"))
    )
    (net (code "85") (name "unconnected-(IC6-RDY{slash}CLK-Pad2)") (class "Default")
      (node (ref "IC6") (pin "2") (pinfunction "RDY/CLK_2") (pintype "output"))
    )
    (net (code "86") (name "unconnected-(POWER-Pad1)") (class "Default")
      (node (ref "POWER") (pin "1") (pinfunction "1_1") (pintype "passive"))
    )
    (net (code "87") (name "unconnected-(U$1-PWRGD-Pad4)") (class "Default")
      (node (ref "U$1") (pin "4") (pinfunction "PWRGD_4") (pintype "output"))
    )
    (net (code "88") (name "unconnected-(U$4-CARD_DETECT-PadCD)") (class "Default")
      (node (ref "U$4") (pin "CD") (pinfunction "CARD_DETECT_CD") (pintype "passive"))
    )
    (net (code "89") (name "unconnected-(U$4-DAT1-Pad8)") (class "Default")
      (node (ref "U$4") (pin "8") (pinfunction "DAT1_8") (pintype "bidirectional"))
    )
    (net (code "90") (name "unconnected-(U$4-DAT2-Pad9)") (class "Default")
      (node (ref "U$4") (pin "9") (pinfunction "DAT2_9") (pintype "bidirectional"))
    )
    (net (code "91") (name "unconnected-(U$4-WRITE_PROTECT-PadWP)") (class "Default")
      (node (ref "U$4") (pin "WP") (pinfunction "WRITE_PROTECT_WP") (pintype "passive"))
    )
    (net (code "92") (name "unconnected-(U$5-PadID)") (class "Default")
      (node (ref "U$5") (pin "ID") (pinfunction "ID_ID") (pintype "bidirectional"))
    )
    (net (code "93") (name "unconnected-(U2-NC-Pad1)") (class "Default")
      (node (ref "U2") (pin "1") (pinfunction "NC_1") (pintype "bidirectional"))
    )
  )
)
